# sensor.net
KiCad netlist of a schematic drawn in EAGLE
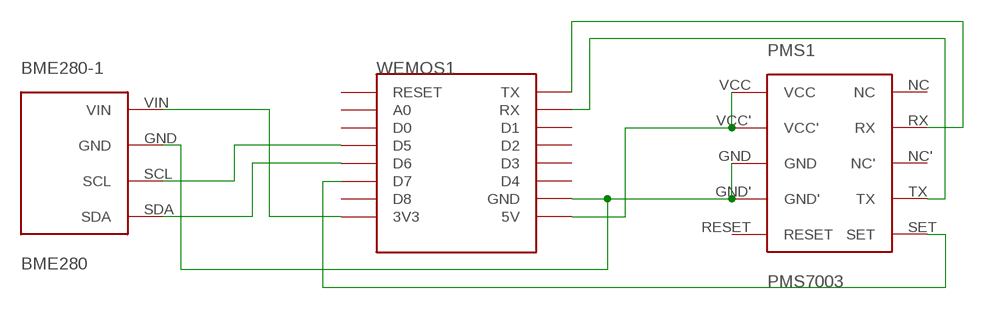
[diagram p0: schematic, sheet 1]

(export (version "E")
  (design (tool "Eeschema 10.0.6"))
  (components
    (comp (ref "BME280-1")
      (value "BME280")
      (footprint "eagle-import:BME280")
      (libsource (lib "eagle-import") (part "BME280"))
    )
    (comp (ref "PMS1")
      (value "PMS7003")
      (footprint "eagle-import:PMS7003")
      (libsource (lib "eagle-import") (part "PMS7003"))
    )
    (comp (ref "WEMOS1")
      (value "WEMOS-D1-MINI")
      (footprint "eagle-import:WEMOS-D1-MINI")
      (libsource (lib "eagle-import") (part "WEMOS-D1-MINI"))
    )
  )
  (nets
    (net (code "1") (name "Net-(BME280-1-PadGND)") (class "Default")
      (node (ref "BME280-1") (pin "GND") (pinfunction "GND_GND") (pintype "bidirectional"))
      (node (ref "PMS1") (pin "GND") (pinfunction "GND_GND") (pintype "bidirectional"))
      (node (ref "PMS1") (pin "GND'") (pinfunction "GND'_GND'") (pintype "bidirectional"))
      (node (ref "WEMOS1") (pin "GND") (pinfunction "GND_GND") (pintype "bidirectional"))
    )
    (net (code "2") (name "Net-(BME280-1-PadSCL)") (class "Default")
      (node (ref "BME280-1") (pin "SCL") (pinfunction "SCL_SCL") (pintype "bidirectional"))
      (node (ref "WEMOS1") (pin "D5") (pinfunction "D5_D5") (pintype "bidirectional"))
    )
    (net (code "3") (name "Net-(BME280-1-PadSDA)") (class "Default")
      (node (ref "BME280-1") (pin "SDA") (pinfunction "SDA_SDA") (pintype "bidirectional"))
      (node (ref "WEMOS1") (pin "D6") (pinfunction "D6_D6") (pintype "bidirectional"))
    )
    (net (code "4") (name "Net-(BME280-1-PadVIN)") (class "Default")
      (node (ref "BME280-1") (pin "VIN") (pinfunction "VIN_VIN") (pintype "bidirectional"))
      (node (ref "WEMOS1") (pin "3V3") (pinfunction "3V3_3V3") (pintype "bidirectional"))
    )
    (net (code "5") (name "Net-(PMS1-PadRX)") (class "Default")
      (node (ref "PMS1") (pin "RX") (pinfunction "RX_RX") (pintype "bidirectional"))
      (node (ref "WEMOS1") (pin "TX") (pinfunction "TX_TX") (pintype "bidirectional"))
    )
    (net (code "6") (name "Net-(PMS1-PadSET)") (class "Default")
      (node (ref "PMS1") (pin "SET") (pinfunction "SET_SET") (pintype "bidirectional"))
      (node (ref "WEMOS1") (pin "D7") (pinfunction "D7_D7") (pintype "bidirectional"))
    )
    (net (code "7") (name "Net-(PMS1-PadTX)") (class "Default")
      (node (ref "PMS1") (pin "TX") (pinfunction "TX_TX") (pintype "bidirectional"))
      (node (ref "WEMOS1") (pin "RX") (pinfunction "RX_RX") (pintype "bidirectional"))
    )
    (net (code "8") (name "Net-(PMS1-PadVCC')") (class "Default")
      (node (ref "PMS1") (pin "VCC") (pinfunction "VCC_VCC") (pintype "bidirectional"))
      (node (ref "PMS1") (pin "VCC'") (pinfunction "VCC'_VCC'") (pintype "bidirectional"))
      (node (ref "WEMOS1") (pin "5V") (pinfunction "5V_5V") (pintype "bidirectional"))
    )
    (net (code "9") (name "unconnected-(PMS1-PadNC')") (class "Default")
      (node (ref "PMS1") (pin "NC'") (pinfunction "NC'_NC'") (pintype "bidirectional"))
    )
    (net (code "10") (name "unconnected-(PMS1-PadNC)") (class "Default")
      (node (ref "PMS1") (pin "NC") (pinfunction "NC_NC") (pintype "bidirectional"))
    )
    (net (code "11") (name "unconnected-(PMS1-PadRESET)") (class "Default")
      (node (ref "PMS1") (pin "RESET") (pinfunction "RESET_RESET") (pintype "bidirectional"))
    )
    (net (code "12") (name "unconnected-(WEMOS1-PadA0)") (class "Default")
      (node (ref "WEMOS1") (pin "A0") (pinfunction "A0_A0") (pintype "bidirectional"))
    )
    (net (code "13") (name "unconnected-(WEMOS1-PadD0)") (class "Default")
      (node (ref "WEMOS1") (pin "D0") (pinfunction "D0_D0") (pintype "bidirectional"))
    )
    (net (code "14") (name "unconnected-(WEMOS1-PadD1)") (class "Default")
      (node (ref "WEMOS1") (pin "D1") (pinfunction "D1_D1") (pintype "bidirectional"))
    )
    (net (code "15") (name "unconnected-(WEMOS1-PadD2)") (class "Default")
      (node (ref "WEMOS1") (pin "D2") (pinfunction "D2_D2") (pintype "bidirectional"))
    )
    (net (code "16") (name "unconnected-(WEMOS1-PadD3)") (class "Default")
      (node (ref "WEMOS1") (pin "D3") (pinfunction "D3_D3") (pintype "bidirectional"))
    )
    (net (code "17") (name "unconnected-(WEMOS1-PadD4)") (class "Default")
      (node (ref "WEMOS1") (pin "D4") (pinfunction "D4_D4") (pintype "bidirectional"))
    )
    (net (code "18") (name "unconnected-(WEMOS1-PadD8)") (class "Default")
      (node (ref "WEMOS1") (pin "D8") (pinfunction "D8_D8") (pintype "bidirectional"))
    )
    (net (code "19") (name "unconnected-(WEMOS1-PadRESET)") (class "Default")
      (node (ref "WEMOS1") (pin "RESET") (pinfunction "RESET_RESET") (pintype "bidirectional"))
    )
  )
)
